# obc-v2_MCU-PinOut.net
KiCad netlist of a schematic drawn in Altium Designer
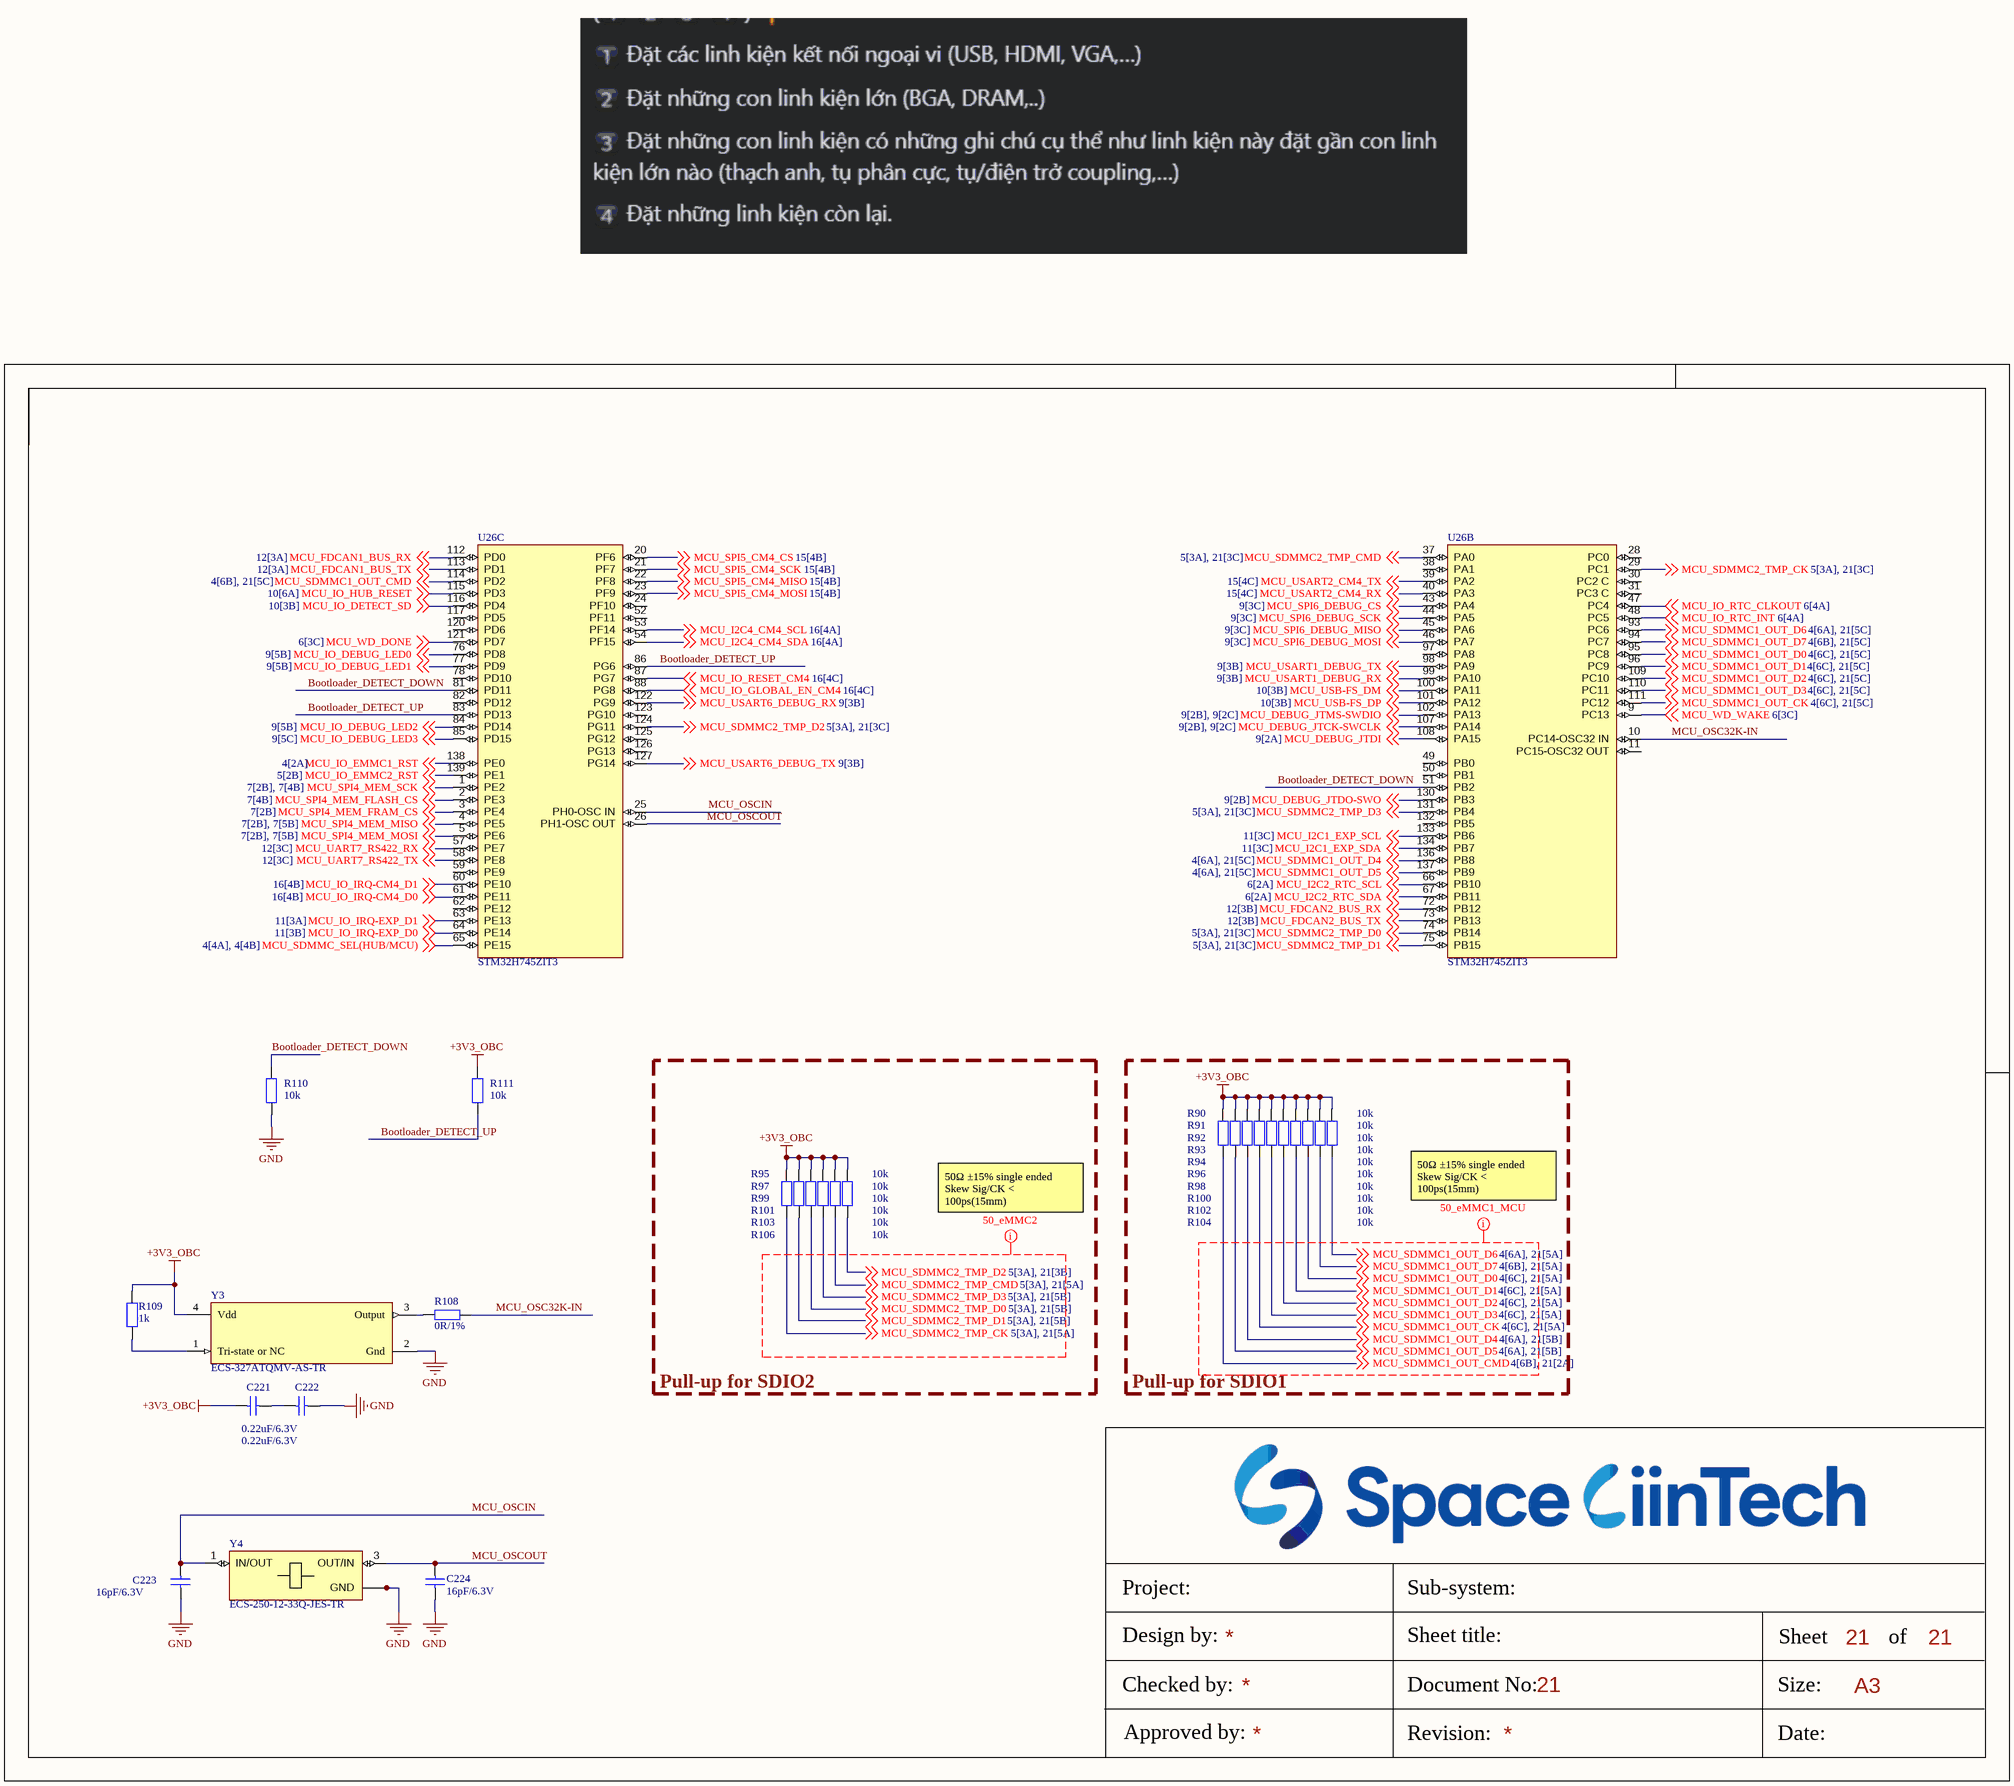
[diagram p0: obc-v2_MCU-PinOut.SchDoc]

(export (version "E")
  (design (tool "Eeschema 10.0.6"))
  (components
    (comp (ref "C221")
      (value "0.22uF/6.3V")
      (footprint "CAP_C_1005X60")
      (description "CAPC")
      (libsource (lib "Altium_Lib_by_KhueNguyenCreator") (part "Tu 0402 33nF 10V"))
    )
    (comp (ref "C222")
      (value "0.22uF/6.3V")
      (footprint "CAP_C_1005X60")
      (description "CAPC")
      (libsource (lib "Altium_Lib_by_KhueNguyenCreator") (part "Tu 0402 33nF 10V"))
    )
    (comp (ref "C223")
      (value "16pF/6.3V")
      (footprint "CAP_C_1005X60")
      (description "CAPC")
      (libsource (lib "Altium_Lib_by_KhueNguyenCreator") (part "Tu 0402 33nF 10V"))
    )
    (comp (ref "C224")
      (value "16pF/6.3V")
      (footprint "CAP_C_1005X60")
      (description "CAPC")
      (libsource (lib "Altium_Lib_by_KhueNguyenCreator") (part "Tu 0402 33nF 10V"))
    )
    (comp (ref "R90")
      (value "10k")
      (footprint "RES_C_1608X60")
      (description "RES 4.7K OHM 1% 1/10W 0603, P/N: ERJ-U03F4701V")
      (libsource (lib "Altium_Lib_by_KhueNguyenCreator") (part "Tro 0603 1% 10k"))
    )
    (comp (ref "R91")
      (value "10k")
      (footprint "RES_C_1608X60")
      (description "RES 4.7K OHM 1% 1/10W 0603, P/N: ERJ-U03F4701V")
      (libsource (lib "Altium_Lib_by_KhueNguyenCreator") (part "Tro 0603 1% 10k"))
    )
    (comp (ref "R92")
      (value "10k")
      (footprint "RES_C_1608X60")
      (description "RES 4.7K OHM 1% 1/10W 0603, P/N: ERJ-U03F4701V")
      (libsource (lib "Altium_Lib_by_KhueNguyenCreator") (part "Tro 0603 1% 10k"))
    )
    (comp (ref "R93")
      (value "10k")
      (footprint "RES_C_1608X60")
      (description "RES 4.7K OHM 1% 1/10W 0603, P/N: ERJ-U03F4701V")
      (libsource (lib "Altium_Lib_by_KhueNguyenCreator") (part "Tro 0603 1% 10k"))
    )
    (comp (ref "R94")
      (value "10k")
      (footprint "RES_C_1608X60")
      (description "RES 4.7K OHM 1% 1/10W 0603, P/N: ERJ-U03F4701V")
      (libsource (lib "Altium_Lib_by_KhueNguyenCreator") (part "Tro 0603 1% 10k"))
    )
    (comp (ref "R95")
      (value "10k")
      (footprint "RES_C_1608X60")
      (description "RES 4.7K OHM 1% 1/10W 0603, P/N: ERJ-U03F4701V")
      (libsource (lib "Altium_Lib_by_KhueNguyenCreator") (part "Tro 0603 1% 10k"))
    )
    (comp (ref "R96")
      (value "10k")
      (footprint "RES_C_1608X60")
      (description "RES 4.7K OHM 1% 1/10W 0603, P/N: ERJ-U03F4701V")
      (libsource (lib "Altium_Lib_by_KhueNguyenCreator") (part "Tro 0603 1% 10k"))
    )
    (comp (ref "R97")
      (value "10k")
      (footprint "RES_C_1608X60")
      (description "RES 4.7K OHM 1% 1/10W 0603, P/N: ERJ-U03F4701V")
      (libsource (lib "Altium_Lib_by_KhueNguyenCreator") (part "Tro 0603 1% 10k"))
    )
    (comp (ref "R98")
      (value "10k")
      (footprint "RES_C_1608X60")
      (description "RES 4.7K OHM 1% 1/10W 0603, P/N: ERJ-U03F4701V")
      (libsource (lib "Altium_Lib_by_KhueNguyenCreator") (part "Tro 0603 1% 10k"))
    )
    (comp (ref "R99")
      (value "10k")
      (footprint "RES_C_1608X60")
      (description "RES 4.7K OHM 1% 1/10W 0603, P/N: ERJ-U03F4701V")
      (libsource (lib "Altium_Lib_by_KhueNguyenCreator") (part "Tro 0603 1% 10k"))
    )
    (comp (ref "R100")
      (value "10k")
      (footprint "RES_C_1608X60")
      (description "RES 4.7K OHM 1% 1/10W 0603, P/N: ERJ-U03F4701V")
      (libsource (lib "Altium_Lib_by_KhueNguyenCreator") (part "Tro 0603 1% 10k"))
    )
    (comp (ref "R101")
      (value "10k")
      (footprint "RES_C_1608X60")
      (description "RES 4.7K OHM 1% 1/10W 0603, P/N: ERJ-U03F4701V")
      (libsource (lib "Altium_Lib_by_KhueNguyenCreator") (part "Tro 0603 1% 10k"))
    )
    (comp (ref "R102")
      (value "10k")
      (footprint "RES_C_1608X60")
      (description "RES 4.7K OHM 1% 1/10W 0603, P/N: ERJ-U03F4701V")
      (libsource (lib "Altium_Lib_by_KhueNguyenCreator") (part "Tro 0603 1% 10k"))
    )
    (comp (ref "R103")
      (value "10k")
      (footprint "RES_C_1608X60")
      (description "RES 4.7K OHM 1% 1/10W 0603, P/N: ERJ-U03F4701V")
      (libsource (lib "Altium_Lib_by_KhueNguyenCreator") (part "Tro 0603 1% 10k"))
    )
    (comp (ref "R104")
      (value "10k")
      (footprint "RES_C_1608X60")
      (description "RES 4.7K OHM 1% 1/10W 0603, P/N: ERJ-U03F4701V")
      (libsource (lib "Altium_Lib_by_KhueNguyenCreator") (part "Tro 0603 1% 10k"))
    )
    (comp (ref "R106")
      (value "10k")
      (footprint "RES_C_1608X60")
      (description "RES 4.7K OHM 1% 1/10W 0603, P/N: ERJ-U03F4701V")
      (libsource (lib "Altium_Lib_by_KhueNguyenCreator") (part "Tro 0603 1% 10k"))
    )
    (comp (ref "R108")
      (value "0R/1%")
      (footprint "RES_C_1608X60")
      (description "RES")
      (libsource (lib "Altium_Lib_by_KhueNguyenCreator") (part "Tro 0603 1% 10k"))
    )
    (comp (ref "R109")
      (value "1k")
      (footprint "RES_C_1608X60")
      (description "RES")
      (libsource (lib "Altium_Lib_by_KhueNguyenCreator") (part "Tro 0603 1% 10k"))
    )
    (comp (ref "R110")
      (value "10k")
      (footprint "RES_C_1608X60")
      (description "RES 4.7K OHM 1% 1/10W 0603, P/N: ERJ-U03F4701V")
      (libsource (lib "Altium_Lib_by_KhueNguyenCreator") (part "Tro 0603 1% 10k"))
    )
    (comp (ref "R111")
      (value "10k")
      (footprint "RES_C_1608X60")
      (description "RES 4.7K OHM 1% 1/10W 0603, P/N: ERJ-U03F4701V")
      (libsource (lib "Altium_Lib_by_KhueNguyenCreator") (part "Tro 0603 1% 10k"))
    )
    (comp (ref "U26")
      (value "STM32H745ZIT3")
      (footprint "FP-LQFP144-1A-MFG")
      (description "HIGH-PERFORMANCE AND DSP WITH DP")
      (fields
        (field (name "MANUFACTURER PART NUMBER") "STM32H745ZIT6")
        (field (name "OCTOPART") "https://octopart.com/stm32h745zit6-stmicroelectronics-100293939")
      )
      (libsource (lib "Altium Content Vault") (part "f5432ce9894f79c0085309acf87c031"))
    )
    (comp (ref "Y3")
      (value "ECS-327ATQMV-AS-TR")
      (footprint "FP-327ATQMV-MFG")
      (description "XTAL OSC XO 32.7680KHZ CMOS SMD")
      (libsource (lib "Altium Content Vault") (part "48575ee33648fc99c8f9879a7ebcfb2"))
    )
    (comp (ref "Y4")
      (value "ECS-250-12-33Q-JES-TR")
      (footprint "XTAL_ECS-250-12-33Q-JES-TR")
      (description "25 MHz Â±20ppm Crystal 12pF 40 Ohms 4-SMD, No Lead")
      (fields (field (name "MF") "ECS Inc."))
      (libsource (lib "ECS-250-12-33Q-JES-TR") (part "ECS-250-12-33Q-JES-TR"))
    )
  )
  (nets
    (net (code "1") (name "+3V3_OBC") (class "Default")
      (node (ref "C221") (pin "1") (pinfunction "1_1") (pintype "passive"))
      (node (ref "R100") (pin "2") (pinfunction "2_2") (pintype "passive"))
      (node (ref "R101") (pin "2") (pinfunction "2_2") (pintype "passive"))
      (node (ref "R102") (pin "2") (pinfunction "2_2") (pintype "passive"))
      (node (ref "R103") (pin "2") (pinfunction "2_2") (pintype "passive"))
      (node (ref "R104") (pin "2") (pinfunction "2_2") (pintype "passive"))
      (node (ref "R106") (pin "2") (pinfunction "2_2") (pintype "passive"))
      (node (ref "R109") (pin "1") (pinfunction "1_1") (pintype "passive"))
      (node (ref "R111") (pin "2") (pinfunction "2_2") (pintype "passive"))
      (node (ref "R90") (pin "2") (pinfunction "2_2") (pintype "passive"))
      (node (ref "R91") (pin "2") (pinfunction "2_2") (pintype "passive"))
      (node (ref "R92") (pin "2") (pinfunction "2_2") (pintype "passive"))
      (node (ref "R93") (pin "2") (pinfunction "2_2") (pintype "passive"))
      (node (ref "R94") (pin "2") (pinfunction "2_2") (pintype "passive"))
      (node (ref "R95") (pin "2") (pinfunction "2_2") (pintype "passive"))
      (node (ref "R96") (pin "2") (pinfunction "2_2") (pintype "passive"))
      (node (ref "R97") (pin "2") (pinfunction "2_2") (pintype "passive"))
      (node (ref "R98") (pin "2") (pinfunction "2_2") (pintype "passive"))
      (node (ref "R99") (pin "2") (pinfunction "2_2") (pintype "passive"))
      (node (ref "Y3") (pin "4") (pinfunction "Vdd_4") (pintype "power_in"))
    )
    (net (code "2") (name "/Bootloader_DETECT_DOWN") (class "Default")
      (node (ref "R110") (pin "2") (pinfunction "2_2") (pintype "passive"))
      (node (ref "U26") (pin "51") (pinfunction "PB2_51") (pintype "bidirectional"))
      (node (ref "U26") (pin "81") (pinfunction "PD11_81") (pintype "bidirectional"))
    )
    (net (code "3") (name "/Bootloader_DETECT_UP") (class "Default")
      (node (ref "R111") (pin "1") (pinfunction "1_1") (pintype "passive"))
      (node (ref "U26") (pin "83") (pinfunction "PD13_83") (pintype "bidirectional"))
      (node (ref "U26") (pin "86") (pinfunction "PG6_86") (pintype "bidirectional"))
    )
    (net (code "4") (name "/MCU_OSC32K-IN") (class "Default")
      (node (ref "R108") (pin "1") (pinfunction "1_1") (pintype "passive"))
      (node (ref "U26") (pin "10") (pinfunction "PC14-OSC32_IN_10") (pintype "bidirectional"))
    )
    (net (code "5") (name "/MCU_OSCIN") (class "Default")
      (node (ref "C223") (pin "2") (pinfunction "2_2") (pintype "passive"))
      (node (ref "U26") (pin "25") (pinfunction "PH0-OSC_IN_25") (pintype "bidirectional"))
      (node (ref "Y4") (pin "1") (pinfunction "IN/OUT_1") (pintype "bidirectional"))
    )
    (net (code "6") (name "/MCU_OSCOUT") (class "Default")
      (node (ref "C224") (pin "2") (pinfunction "2_2") (pintype "passive"))
      (node (ref "U26") (pin "26") (pinfunction "PH1-OSC_OUT_26") (pintype "bidirectional"))
      (node (ref "Y4") (pin "3") (pinfunction "OUT/IN_3") (pintype "bidirectional"))
    )
    (net (code "7") (name "GND") (class "Default")
      (node (ref "C222") (pin "2") (pinfunction "2_2") (pintype "passive"))
      (node (ref "C223") (pin "1") (pinfunction "1_1") (pintype "passive"))
      (node (ref "C224") (pin "1") (pinfunction "1_1") (pintype "passive"))
      (node (ref "R110") (pin "1") (pinfunction "1_1") (pintype "passive"))
      (node (ref "Y3") (pin "2") (pinfunction "Gnd_2") (pintype "power_in"))
      (node (ref "Y4") (pin "2") (pinfunction "GND_2") (pintype "power_in"))
      (node (ref "Y4") (pin "4") (pinfunction "GND_4") (pintype "power_in"))
    )
    (net (code "8") (name "MCU_DEBUG_JTCK-SWCLK") (class "Default")
      (node (ref "U26") (pin "107") (pinfunction "PA14_107") (pintype "bidirectional"))
    )
    (net (code "9") (name "MCU_DEBUG_JTDI") (class "Default")
      (node (ref "U26") (pin "108") (pinfunction "PA15_108") (pintype "bidirectional"))
    )
    (net (code "10") (name "MCU_DEBUG_JTDO-SWO") (class "Default")
      (node (ref "U26") (pin "130") (pinfunction "PB3_130") (pintype "bidirectional"))
    )
    (net (code "11") (name "MCU_DEBUG_JTMS-SWDIO") (class "Default")
      (node (ref "U26") (pin "102") (pinfunction "PA13_102") (pintype "bidirectional"))
    )
    (net (code "12") (name "MCU_FDCAN1_BUS_RX") (class "Default")
      (node (ref "U26") (pin "112") (pinfunction "PD0_112") (pintype "bidirectional"))
    )
    (net (code "13") (name "MCU_FDCAN1_BUS_TX") (class "Default")
      (node (ref "U26") (pin "113") (pinfunction "PD1_113") (pintype "bidirectional"))
    )
    (net (code "14") (name "MCU_FDCAN2_BUS_RX") (class "Default")
      (node (ref "U26") (pin "72") (pinfunction "PB12_72") (pintype "bidirectional"))
    )
    (net (code "15") (name "MCU_FDCAN2_BUS_TX") (class "Default")
      (node (ref "U26") (pin "73") (pinfunction "PB13_73") (pintype "bidirectional"))
    )
    (net (code "16") (name "MCU_I2C1_EXP_SCL") (class "Default")
      (node (ref "U26") (pin "133") (pinfunction "PB6_133") (pintype "bidirectional"))
    )
    (net (code "17") (name "MCU_I2C1_EXP_SDA") (class "Default")
      (node (ref "U26") (pin "134") (pinfunction "PB7_134") (pintype "bidirectional"))
    )
    (net (code "18") (name "MCU_I2C2_RTC_SCL") (class "Default")
      (node (ref "U26") (pin "66") (pinfunction "PB10_66") (pintype "bidirectional"))
    )
    (net (code "19") (name "MCU_I2C2_RTC_SDA") (class "Default")
      (node (ref "U26") (pin "67") (pinfunction "PB11_67") (pintype "bidirectional"))
    )
    (net (code "20") (name "MCU_I2C4_CM4_SCL") (class "Default")
      (node (ref "U26") (pin "53") (pinfunction "PF14_53") (pintype "bidirectional"))
    )
    (net (code "21") (name "MCU_I2C4_CM4_SDA") (class "Default")
      (node (ref "U26") (pin "54") (pinfunction "PF15_54") (pintype "bidirectional"))
    )
    (net (code "22") (name "MCU_IO_DEBUG_LED0") (class "Default")
      (node (ref "U26") (pin "76") (pinfunction "PD8_76") (pintype "bidirectional"))
    )
    (net (code "23") (name "MCU_IO_DEBUG_LED1") (class "Default")
      (node (ref "U26") (pin "77") (pinfunction "PD9_77") (pintype "bidirectional"))
    )
    (net (code "24") (name "MCU_IO_DEBUG_LED2") (class "Default")
      (node (ref "U26") (pin "84") (pinfunction "PD14_84") (pintype "bidirectional"))
    )
    (net (code "25") (name "MCU_IO_DEBUG_LED3") (class "Default")
      (node (ref "U26") (pin "85") (pinfunction "PD15_85") (pintype "bidirectional"))
    )
    (net (code "26") (name "MCU_IO_DETECT_SD") (class "Default")
      (node (ref "U26") (pin "116") (pinfunction "PD4_116") (pintype "bidirectional"))
    )
    (net (code "27") (name "MCU_IO_EMMC1_RST") (class "Default")
      (node (ref "U26") (pin "138") (pinfunction "PE0_138") (pintype "bidirectional"))
    )
    (net (code "28") (name "MCU_IO_EMMC2_RST") (class "Default")
      (node (ref "U26") (pin "139") (pinfunction "PE1_139") (pintype "bidirectional"))
    )
    (net (code "29") (name "MCU_IO_GLOBAL_EN_CM4") (class "Default")
      (node (ref "U26") (pin "88") (pinfunction "PG8_88") (pintype "bidirectional"))
    )
    (net (code "30") (name "MCU_IO_HUB_RESET") (class "Default")
      (node (ref "U26") (pin "115") (pinfunction "PD3_115") (pintype "bidirectional"))
    )
    (net (code "31") (name "MCU_IO_IRQ-CM4_D0") (class "Default")
      (node (ref "U26") (pin "61") (pinfunction "PE11_61") (pintype "bidirectional"))
    )
    (net (code "32") (name "MCU_IO_IRQ-CM4_D1") (class "Default")
      (node (ref "U26") (pin "60") (pinfunction "PE10_60") (pintype "bidirectional"))
    )
    (net (code "33") (name "MCU_IO_IRQ-EXP_D0") (class "Default")
      (node (ref "U26") (pin "64") (pinfunction "PE14_64") (pintype "bidirectional"))
    )
    (net (code "34") (name "MCU_IO_IRQ-EXP_D1") (class "Default")
      (node (ref "U26") (pin "63") (pinfunction "PE13_63") (pintype "bidirectional"))
    )
    (net (code "35") (name "MCU_IO_RESET_CM4") (class "Default")
      (node (ref "U26") (pin "87") (pinfunction "PG7_87") (pintype "bidirectional"))
    )
    (net (code "36") (name "MCU_IO_RTC_CLKOUT") (class "Default")
      (node (ref "U26") (pin "47") (pinfunction "PC4_47") (pintype "bidirectional"))
    )
    (net (code "37") (name "MCU_IO_RTC_INT") (class "Default")
      (node (ref "U26") (pin "48") (pinfunction "PC5_48") (pintype "bidirectional"))
    )
    (net (code "38") (name "MCU_SDMMC1_OUT_CK") (class "Default")
      (node (ref "R93") (pin "1") (pinfunction "1_1") (pintype "passive"))
      (node (ref "U26") (pin "111") (pinfunction "PC12_111") (pintype "bidirectional"))
    )
    (net (code "39") (name "MCU_SDMMC1_OUT_CMD") (class "Default")
      (node (ref "R90") (pin "1") (pinfunction "1_1") (pintype "passive"))
      (node (ref "U26") (pin "114") (pinfunction "PD2_114") (pintype "bidirectional"))
    )
    (net (code "40") (name "MCU_SDMMC1_OUT_D0") (class "Default")
      (node (ref "R100") (pin "1") (pinfunction "1_1") (pintype "passive"))
      (node (ref "U26") (pin "95") (pinfunction "PC8_95") (pintype "bidirectional"))
    )
    (net (code "41") (name "MCU_SDMMC1_OUT_D1") (class "Default")
      (node (ref "R98") (pin "1") (pinfunction "1_1") (pintype "passive"))
      (node (ref "U26") (pin "96") (pinfunction "PC9_96") (pintype "bidirectional"))
    )
    (net (code "42") (name "MCU_SDMMC1_OUT_D2") (class "Default")
      (node (ref "R96") (pin "1") (pinfunction "1_1") (pintype "passive"))
      (node (ref "U26") (pin "109") (pinfunction "PC10_109") (pintype "bidirectional"))
    )
    (net (code "43") (name "MCU_SDMMC1_OUT_D3") (class "Default")
      (node (ref "R94") (pin "1") (pinfunction "1_1") (pintype "passive"))
      (node (ref "U26") (pin "110") (pinfunction "PC11_110") (pintype "bidirectional"))
    )
    (net (code "44") (name "MCU_SDMMC1_OUT_D4") (class "Default")
      (node (ref "R92") (pin "1") (pinfunction "1_1") (pintype "passive"))
      (node (ref "U26") (pin "136") (pinfunction "PB8_136") (pintype "bidirectional"))
    )
    (net (code "45") (name "MCU_SDMMC1_OUT_D5") (class "Default")
      (node (ref "R91") (pin "1") (pinfunction "1_1") (pintype "passive"))
      (node (ref "U26") (pin "137") (pinfunction "PB9_137") (pintype "bidirectional"))
    )
    (net (code "46") (name "MCU_SDMMC1_OUT_D6") (class "Default")
      (node (ref "R104") (pin "1") (pinfunction "1_1") (pintype "passive"))
      (node (ref "U26") (pin "93") (pinfunction "PC6_93") (pintype "bidirectional"))
    )
    (net (code "47") (name "MCU_SDMMC1_OUT_D7") (class "Default")
      (node (ref "R102") (pin "1") (pinfunction "1_1") (pintype "passive"))
      (node (ref "U26") (pin "94") (pinfunction "PC7_94") (pintype "bidirectional"))
    )
    (net (code "48") (name "MCU_SDMMC2_TMP_CK") (class "Default")
      (node (ref "R95") (pin "1") (pinfunction "1_1") (pintype "passive"))
      (node (ref "U26") (pin "29") (pinfunction "PC1_29") (pintype "bidirectional"))
    )
    (net (code "49") (name "MCU_SDMMC2_TMP_CMD") (class "Default")
      (node (ref "R103") (pin "1") (pinfunction "1_1") (pintype "passive"))
      (node (ref "U26") (pin "37") (pinfunction "PA0_37") (pintype "bidirectional"))
    )
    (net (code "50") (name "MCU_SDMMC2_TMP_D0") (class "Default")
      (node (ref "R99") (pin "1") (pinfunction "1_1") (pintype "passive"))
      (node (ref "U26") (pin "74") (pinfunction "PB14_74") (pintype "bidirectional"))
    )
    (net (code "51") (name "MCU_SDMMC2_TMP_D1") (class "Default")
      (node (ref "R97") (pin "1") (pinfunction "1_1") (pintype "passive"))
      (node (ref "U26") (pin "75") (pinfunction "PB15_75") (pintype "bidirectional"))
    )
    (net (code "52") (name "MCU_SDMMC2_TMP_D2") (class "Default")
      (node (ref "R106") (pin "1") (pinfunction "1_1") (pintype "passive"))
      (node (ref "U26") (pin "124") (pinfunction "PG11_124") (pintype "bidirectional"))
    )
    (net (code "53") (name "MCU_SDMMC2_TMP_D3") (class "Default")
      (node (ref "R101") (pin "1") (pinfunction "1_1") (pintype "passive"))
      (node (ref "U26") (pin "131") (pinfunction "PB4_131") (pintype "bidirectional"))
    )
    (net (code "54") (name "MCU_SDMMC_SEL(HUB{slash}MCU)") (class "Default")
      (node (ref "U26") (pin "65") (pinfunction "PE15_65") (pintype "bidirectional"))
    )
    (net (code "55") (name "MCU_SPI4_MEM_FLASH_CS") (class "Default")
      (node (ref "U26") (pin "2") (pinfunction "PE3_2") (pintype "bidirectional"))
    )
    (net (code "56") (name "MCU_SPI4_MEM_FRAM_CS") (class "Default")
      (node (ref "U26") (pin "3") (pinfunction "PE4_3") (pintype "bidirectional"))
    )
    (net (code "57") (name "MCU_SPI4_MEM_MISO") (class "Default")
      (node (ref "U26") (pin "4") (pinfunction "PE5_4") (pintype "bidirectional"))
    )
    (net (code "58") (name "MCU_SPI4_MEM_MOSI") (class "Default")
      (node (ref "U26") (pin "5") (pinfunction "PE6_5") (pintype "bidirectional"))
    )
    (net (code "59") (name "MCU_SPI4_MEM_SCK") (class "Default")
      (node (ref "U26") (pin "1") (pinfunction "PE2_1") (pintype "bidirectional"))
    )
    (net (code "60") (name "MCU_SPI5_CM4_CS") (class "Default")
      (node (ref "U26") (pin "20") (pinfunction "PF6_20") (pintype "bidirectional"))
    )
    (net (code "61") (name "MCU_SPI5_CM4_MISO") (class "Default")
      (node (ref "U26") (pin "22") (pinfunction "PF8_22") (pintype "bidirectional"))
    )
    (net (code "62") (name "MCU_SPI5_CM4_MOSI") (class "Default")
      (node (ref "U26") (pin "23") (pinfunction "PF9_23") (pintype "bidirectional"))
    )
    (net (code "63") (name "MCU_SPI5_CM4_SCK") (class "Default")
      (node (ref "U26") (pin "21") (pinfunction "PF7_21") (pintype "bidirectional"))
    )
    (net (code "64") (name "MCU_SPI6_DEBUG_CS") (class "Default")
      (node (ref "U26") (pin "43") (pinfunction "PA4_43") (pintype "bidirectional"))
    )
    (net (code "65") (name "MCU_SPI6_DEBUG_MISO") (class "Default")
      (node (ref "U26") (pin "45") (pinfunction "PA6_45") (pintype "bidirectional"))
    )
    (net (code "66") (name "MCU_SPI6_DEBUG_MOSI") (class "Default")
      (node (ref "U26") (pin "46") (pinfunction "PA7_46") (pintype "bidirectional"))
    )
    (net (code "67") (name "MCU_SPI6_DEBUG_SCK") (class "Default")
      (node (ref "U26") (pin "44") (pinfunction "PA5_44") (pintype "bidirectional"))
    )
    (net (code "68") (name "MCU_UART7_RS422_RX") (class "Default")
      (node (ref "U26") (pin "57") (pinfunction "PE7_57") (pintype "bidirectional"))
    )
    (net (code "69") (name "MCU_UART7_RS422_TX") (class "Default")
      (node (ref "U26") (pin "58") (pinfunction "PE8_58") (pintype "bidirectional"))
    )
    (net (code "70") (name "MCU_USART1_DEBUG_RX") (class "Default")
      (node (ref "U26") (pin "99") (pinfunction "PA10_99") (pintype "bidirectional"))
    )
    (net (code "71") (name "MCU_USART1_DEBUG_TX") (class "Default")
      (node (ref "U26") (pin "98") (pinfunction "PA9_98") (pintype "bidirectional"))
    )
    (net (code "72") (name "MCU_USART2_CM4_RX") (class "Default")
      (node (ref "U26") (pin "40") (pinfunction "PA3_40") (pintype "bidirectional"))
    )
    (net (code "73") (name "MCU_USART2_CM4_TX") (class "Default")
      (node (ref "U26") (pin "39") (pinfunction "PA2_39") (pintype "bidirectional"))
    )
    (net (code "74") (name "MCU_USART6_DEBUG_RX") (class "Default")
      (node (ref "U26") (pin "122") (pinfunction "PG9_122") (pintype "bidirectional"))
    )
    (net (code "75") (name "MCU_USART6_DEBUG_TX") (class "Default")
      (node (ref "U26") (pin "127") (pinfunction "PG14_127") (pintype "bidirectional"))
    )
    (net (code "76") (name "MCU_USB-FS_DM") (class "Default")
      (node (ref "U26") (pin "100") (pinfunction "PA11_100") (pintype "bidirectional"))
    )
    (net (code "77") (name "MCU_USB-FS_DP") (class "Default")
      (node (ref "U26") (pin "101") (pinfunction "PA12_101") (pintype "bidirectional"))
    )
    (net (code "78") (name "MCU_WD_DONE") (class "Default")
      (node (ref "U26") (pin "121") (pinfunction "PD7_121") (pintype "bidirectional"))
    )
    (net (code "79") (name "MCU_WD_WAKE") (class "Default")
      (node (ref "U26") (pin "9") (pinfunction "PC13_9") (pintype "bidirectional"))
    )
    (net (code "80") (name "Net-(C221-Pad2)") (class "Default")
      (node (ref "C221") (pin "2") (pinfunction "2_2") (pintype "passive"))
      (node (ref "C222") (pin "1") (pinfunction "1_1") (pintype "passive"))
    )
    (net (code "81") (name "Net-(Y3-Output)") (class "Default")
      (node (ref "R108") (pin "2") (pinfunction "2_2") (pintype "passive"))
      (node (ref "Y3") (pin "3") (pinfunction "Output_3") (pintype "output"))
    )
    (net (code "82") (name "Net-(Y3-Tri-state_or_NC)") (class "Default")
      (node (ref "R109") (pin "2") (pinfunction "2_2") (pintype "passive"))
      (node (ref "Y3") (pin "1") (pinfunction "Tri-state_or_NC_1") (pintype "input"))
    )
    (net (code "83") (name "unconnected-(U26B-PA1-Pad38)") (class "Default")
      (node (ref "U26") (pin "38") (pinfunction "PA1_38") (pintype "bidirectional"))
    )
    (net (code "84") (name "unconnected-(U26B-PA8-Pad97)") (class "Default")
      (node (ref "U26") (pin "97") (pinfunction "PA8_97") (pintype "bidirectional"))
    )
    (net (code "85") (name "unconnected-(U26B-PB0-Pad49)") (class "Default")
      (node (ref "U26") (pin "49") (pinfunction "PB0_49") (pintype "bidirectional"))
    )
    (net (code "86") (name "unconnected-(U26B-PB1-Pad50)") (class "Default")
      (node (ref "U26") (pin "50") (pinfunction "PB1_50") (pintype "bidirectional"))
    )
    (net (code "87") (name "unconnected-(U26B-PB5-Pad132)") (class "Default")
      (node (ref "U26") (pin "132") (pinfunction "PB5_132") (pintype "bidirectional"))
    )
    (net (code "88") (name "unconnected-(U26B-PC0-Pad28)") (class "Default")
      (node (ref "U26") (pin "28") (pinfunction "PC0_28") (pintype "bidirectional"))
    )
    (net (code "89") (name "unconnected-(U26B-PC2_C-Pad30)") (class "Default")
      (node (ref "U26") (pin "30") (pinfunction "PC2_C_30") (pintype "bidirectional"))
    )
    (net (code "90") (name "unconnected-(U26B-PC3_C-Pad31)") (class "Default")
      (node (ref "U26") (pin "31") (pinfunction "PC3_C_31") (pintype "bidirectional"))
    )
    (net (code "91") (name "unconnected-(U26B-PC15-OSC32_OUT-Pad11)") (class "Default")
      (node (ref "U26") (pin "11") (pinfunction "PC15-OSC32_OUT_11") (pintype "bidirectional"))
    )
    (net (code "92") (name "unconnected-(U26C-PD5-Pad117)") (class "Default")
      (node (ref "U26") (pin "117") (pinfunction "PD5_117") (pintype "bidirectional"))
    )
    (net (code "93") (name "unconnected-(U26C-PD6-Pad120)") (class "Default")
      (node (ref "U26") (pin "120") (pinfunction "PD6_120") (pintype "bidirectional"))
    )
    (net (code "94") (name "unconnected-(U26C-PD10-Pad78)") (class "Default")
      (node (ref "U26") (pin "78") (pinfunction "PD10_78") (pintype "bidirectional"))
    )
    (net (code "95") (name "unconnected-(U26C-PD12-Pad82)") (class "Default")
      (node (ref "U26") (pin "82") (pinfunction "PD12_82") (pintype "bidirectional"))
    )
    (net (code "96") (name "unconnected-(U26C-PE9-Pad59)") (class "Default")
      (node (ref "U26") (pin "59") (pinfunction "PE9_59") (pintype "bidirectional"))
    )
    (net (code "97") (name "unconnected-(U26C-PE12-Pad62)") (class "Default")
      (node (ref "U26") (pin "62") (pinfunction "PE12_62") (pintype "bidirectional"))
    )
    (net (code "98") (name "unconnected-(U26C-PF10-Pad24)") (class "Default")
      (node (ref "U26") (pin "24") (pinfunction "PF10_24") (pintype "bidirectional"))
    )
    (net (code "99") (name "unconnected-(U26C-PF11-Pad52)") (class "Default")
      (node (ref "U26") (pin "52") (pinfunction "PF11_52") (pintype "bidirectional"))
    )
    (net (code "100") (name "unconnected-(U26C-PG10-Pad123)") (class "Default")
      (node (ref "U26") (pin "123") (pinfunction "PG10_123") (pintype "bidirectional"))
    )
    (net (code "101") (name "unconnected-(U26C-PG12-Pad125)") (class "Default")
      (node (ref "U26") (pin "125") (pinfunction "PG12_125") (pintype "bidirectional"))
    )
    (net (code "102") (name "unconnected-(U26C-PG13-Pad126)") (class "Default")
      (node (ref "U26") (pin "126") (pinfunction "PG13_126") (pintype "bidirectional"))
    )
  )
)
